# tiny85.net
KiCad netlist of a schematic drawn in EAGLE
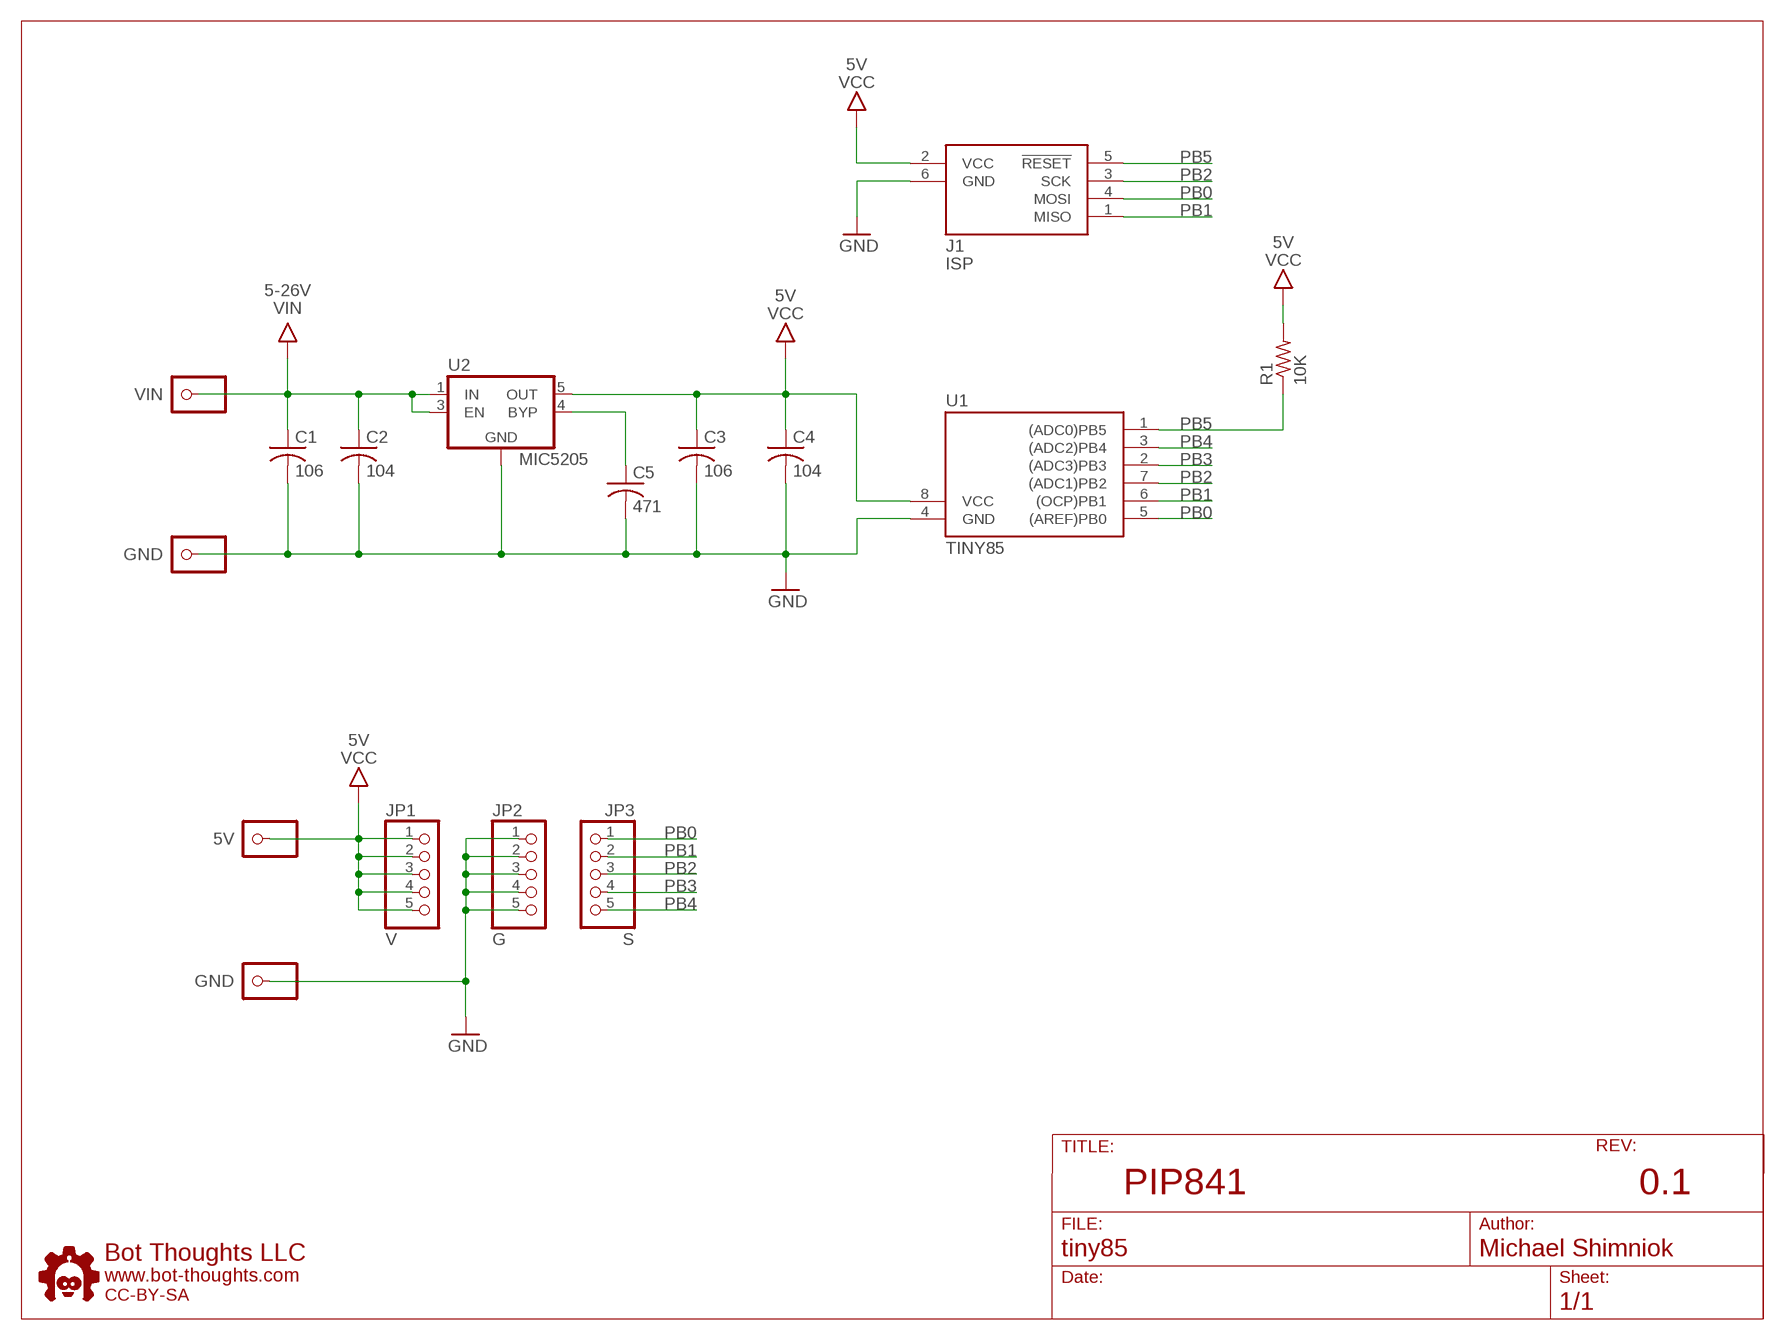
[diagram p0: schematic, sheet 1]

(export (version "E")
  (design (tool "Eeschema 10.0.6"))
  (components
    (comp (ref "C1")
      (value "106")
      (footprint "eagle-import:1206")
      (libsource (lib "eagle-import") (part "C-1206"))
    )
    (comp (ref "C2")
      (value "104")
      (footprint "eagle-import:0603")
      (libsource (lib "eagle-import") (part "C-0603"))
    )
    (comp (ref "C3")
      (value "106")
      (footprint "eagle-import:1206")
      (libsource (lib "eagle-import") (part "C-1206"))
    )
    (comp (ref "C4")
      (value "104")
      (footprint "eagle-import:0603")
      (libsource (lib "eagle-import") (part "C-0603"))
    )
    (comp (ref "C5")
      (value "471")
      (footprint "eagle-import:0603")
      (libsource (lib "eagle-import") (part "C-0603"))
    )
    (comp (ref "J1")
      (value "ISP")
      (footprint "eagle-import:CON6P2R")
      (libsource (lib "eagle-import") (part "AVRISP6_COMPACT"))
    )
    (comp (ref "JP1")
      (value "V")
      (footprint "eagle-import:1X05-S")
      (libsource (lib "eagle-import") (part "PINHD-1X05_2.54-S"))
    )
    (comp (ref "JP2")
      (value "G")
      (footprint "eagle-import:1X05-S")
      (libsource (lib "eagle-import") (part "PINHD-1X05_2.54-S"))
    )
    (comp (ref "JP3")
      (value "S")
      (footprint "eagle-import:1X05-S")
      (libsource (lib "eagle-import") (part "PINHD-1X05_2.54-S"))
    )
    (comp (ref "JP4")
      (value "GND")
      (footprint "eagle-import:1X01")
      (libsource (lib "eagle-import") (part "PINHD-1X01_2.54"))
    )
    (comp (ref "JP5")
      (value "VIN")
      (footprint "eagle-import:1X01")
      (libsource (lib "eagle-import") (part "PINHD-1X01_2.54"))
    )
    (comp (ref "JP6")
      (value "GND")
      (footprint "eagle-import:1X01")
      (libsource (lib "eagle-import") (part "PINHD-1X01_2.54"))
    )
    (comp (ref "JP8")
      (value "5V")
      (footprint "eagle-import:1X01")
      (libsource (lib "eagle-import") (part "PINHD-1X01_2.54"))
    )
    (comp (ref "R1")
      (value "10K")
      (footprint "eagle-import:0603")
      (libsource (lib "eagle-import") (part "R0603"))
    )
    (comp (ref "U$3")
      (value "BTLOGO-LOGO-MD")
      (footprint "eagle-import:BTLOGOM")
      (libsource (lib "eagle-import") (part "BTLOGO-LOGO-MD"))
    )
    (comp (ref "U1")
      (value "TINY85")
      (footprint "eagle-import:SOIC8")
      (libsource (lib "eagle-import") (part "TINY25/45/85-20SU"))
    )
    (comp (ref "U2")
      (value "MIC5205")
      (footprint "eagle-import:SOT23-5")
      (libsource (lib "eagle-import") (part "MIC5205"))
    )
  )
  (nets
    (net (code "1") (name "/PB0") (class "Default")
      (node (ref "J1") (pin "4") (pinfunction "MOSI_4") (pintype "output"))
      (node (ref "JP3") (pin "1") (pinfunction "1_1") (pintype "passive"))
      (node (ref "U1") (pin "5") (pinfunction "(AREF)PB0_5") (pintype "bidirectional"))
    )
    (net (code "2") (name "/PB1") (class "Default")
      (node (ref "J1") (pin "1") (pinfunction "MISO_1") (pintype "input"))
      (node (ref "JP3") (pin "2") (pinfunction "2_2") (pintype "passive"))
      (node (ref "U1") (pin "6") (pinfunction "(OCP)PB1_6") (pintype "bidirectional"))
    )
    (net (code "3") (name "/PB2") (class "Default")
      (node (ref "J1") (pin "3") (pinfunction "SCK_3") (pintype "output"))
      (node (ref "JP3") (pin "3") (pinfunction "3_3") (pintype "passive"))
      (node (ref "U1") (pin "7") (pinfunction "(ADC1)PB2_7") (pintype "bidirectional"))
    )
    (net (code "4") (name "/PB3") (class "Default")
      (node (ref "JP3") (pin "4") (pinfunction "4_4") (pintype "passive"))
      (node (ref "U1") (pin "2") (pinfunction "(ADC3)PB3_2") (pintype "bidirectional"))
    )
    (net (code "5") (name "/PB4") (class "Default")
      (node (ref "JP3") (pin "5") (pinfunction "5_5") (pintype "passive"))
      (node (ref "U1") (pin "3") (pinfunction "(ADC2)PB4_3") (pintype "bidirectional"))
    )
    (net (code "6") (name "/PB5") (class "Default")
      (node (ref "J1") (pin "5") (pinfunction "~{RESET}_5") (pintype "output"))
      (node (ref "R1") (pin "1") (pinfunction "1_1") (pintype "passive"))
      (node (ref "U1") (pin "1") (pinfunction "(ADC0)PB5_1") (pintype "bidirectional"))
    )
    (net (code "7") (name "5-26V") (class "Default")
      (node (ref "C1") (pin "1") (pinfunction "+_1") (pintype "passive"))
      (node (ref "C2") (pin "1") (pinfunction "+_1") (pintype "passive"))
      (node (ref "JP5") (pin "1") (pinfunction "1_1") (pintype "passive"))
      (node (ref "U2") (pin "1") (pinfunction "IN_1") (pintype "power_in"))
      (node (ref "U2") (pin "3") (pinfunction "EN_3") (pintype "input"))
    )
    (net (code "8") (name "5V") (class "Default")
      (node (ref "C3") (pin "1") (pinfunction "+_1") (pintype "passive"))
      (node (ref "C4") (pin "1") (pinfunction "+_1") (pintype "passive"))
      (node (ref "J1") (pin "2") (pinfunction "VCC_2") (pintype "power_in"))
      (node (ref "JP1") (pin "1") (pinfunction "1_1") (pintype "passive"))
      (node (ref "JP1") (pin "2") (pinfunction "2_2") (pintype "passive"))
      (node (ref "JP1") (pin "3") (pinfunction "3_3") (pintype "passive"))
      (node (ref "JP1") (pin "4") (pinfunction "4_4") (pintype "passive"))
      (node (ref "JP1") (pin "5") (pinfunction "5_5") (pintype "passive"))
      (node (ref "JP8") (pin "1") (pinfunction "1_1") (pintype "passive"))
      (node (ref "R1") (pin "2") (pinfunction "2_2") (pintype "passive"))
      (node (ref "U1") (pin "8") (pinfunction "VCC_8") (pintype "power_in"))
      (node (ref "U2") (pin "5") (pinfunction "OUT_5") (pintype "power_in"))
    )
    (net (code "9") (name "GND") (class "Default")
      (node (ref "C1") (pin "2") (pinfunction "-_2") (pintype "passive"))
      (node (ref "C2") (pin "2") (pinfunction "-_2") (pintype "passive"))
      (node (ref "C3") (pin "2") (pinfunction "-_2") (pintype "passive"))
      (node (ref "C4") (pin "2") (pinfunction "-_2") (pintype "passive"))
      (node (ref "C5") (pin "2") (pinfunction "-_2") (pintype "passive"))
      (node (ref "J1") (pin "6") (pinfunction "GND_6") (pintype "power_in"))
      (node (ref "JP2") (pin "1") (pinfunction "1_1") (pintype "passive"))
      (node (ref "JP2") (pin "2") (pinfunction "2_2") (pintype "passive"))
      (node (ref "JP2") (pin "3") (pinfunction "3_3") (pintype "passive"))
      (node (ref "JP2") (pin "4") (pinfunction "4_4") (pintype "passive"))
      (node (ref "JP2") (pin "5") (pinfunction "5_5") (pintype "passive"))
      (node (ref "JP4") (pin "1") (pinfunction "1_1") (pintype "passive"))
      (node (ref "JP6") (pin "1") (pinfunction "1_1") (pintype "passive"))
      (node (ref "U1") (pin "4") (pinfunction "GND_4") (pintype "power_in"))
      (node (ref "U2") (pin "2") (pinfunction "GND_2") (pintype "power_in"))
    )
    (net (code "10") (name "Net-(C5-+)") (class "Default")
      (node (ref "C5") (pin "1") (pinfunction "+_1") (pintype "passive"))
      (node (ref "U2") (pin "4") (pinfunction "BYP_4") (pintype "bidirectional"))
    )
  )
)
